# BitBeacon_Emitter.net
KiCad netlist of a schematic drawn in EAGLE
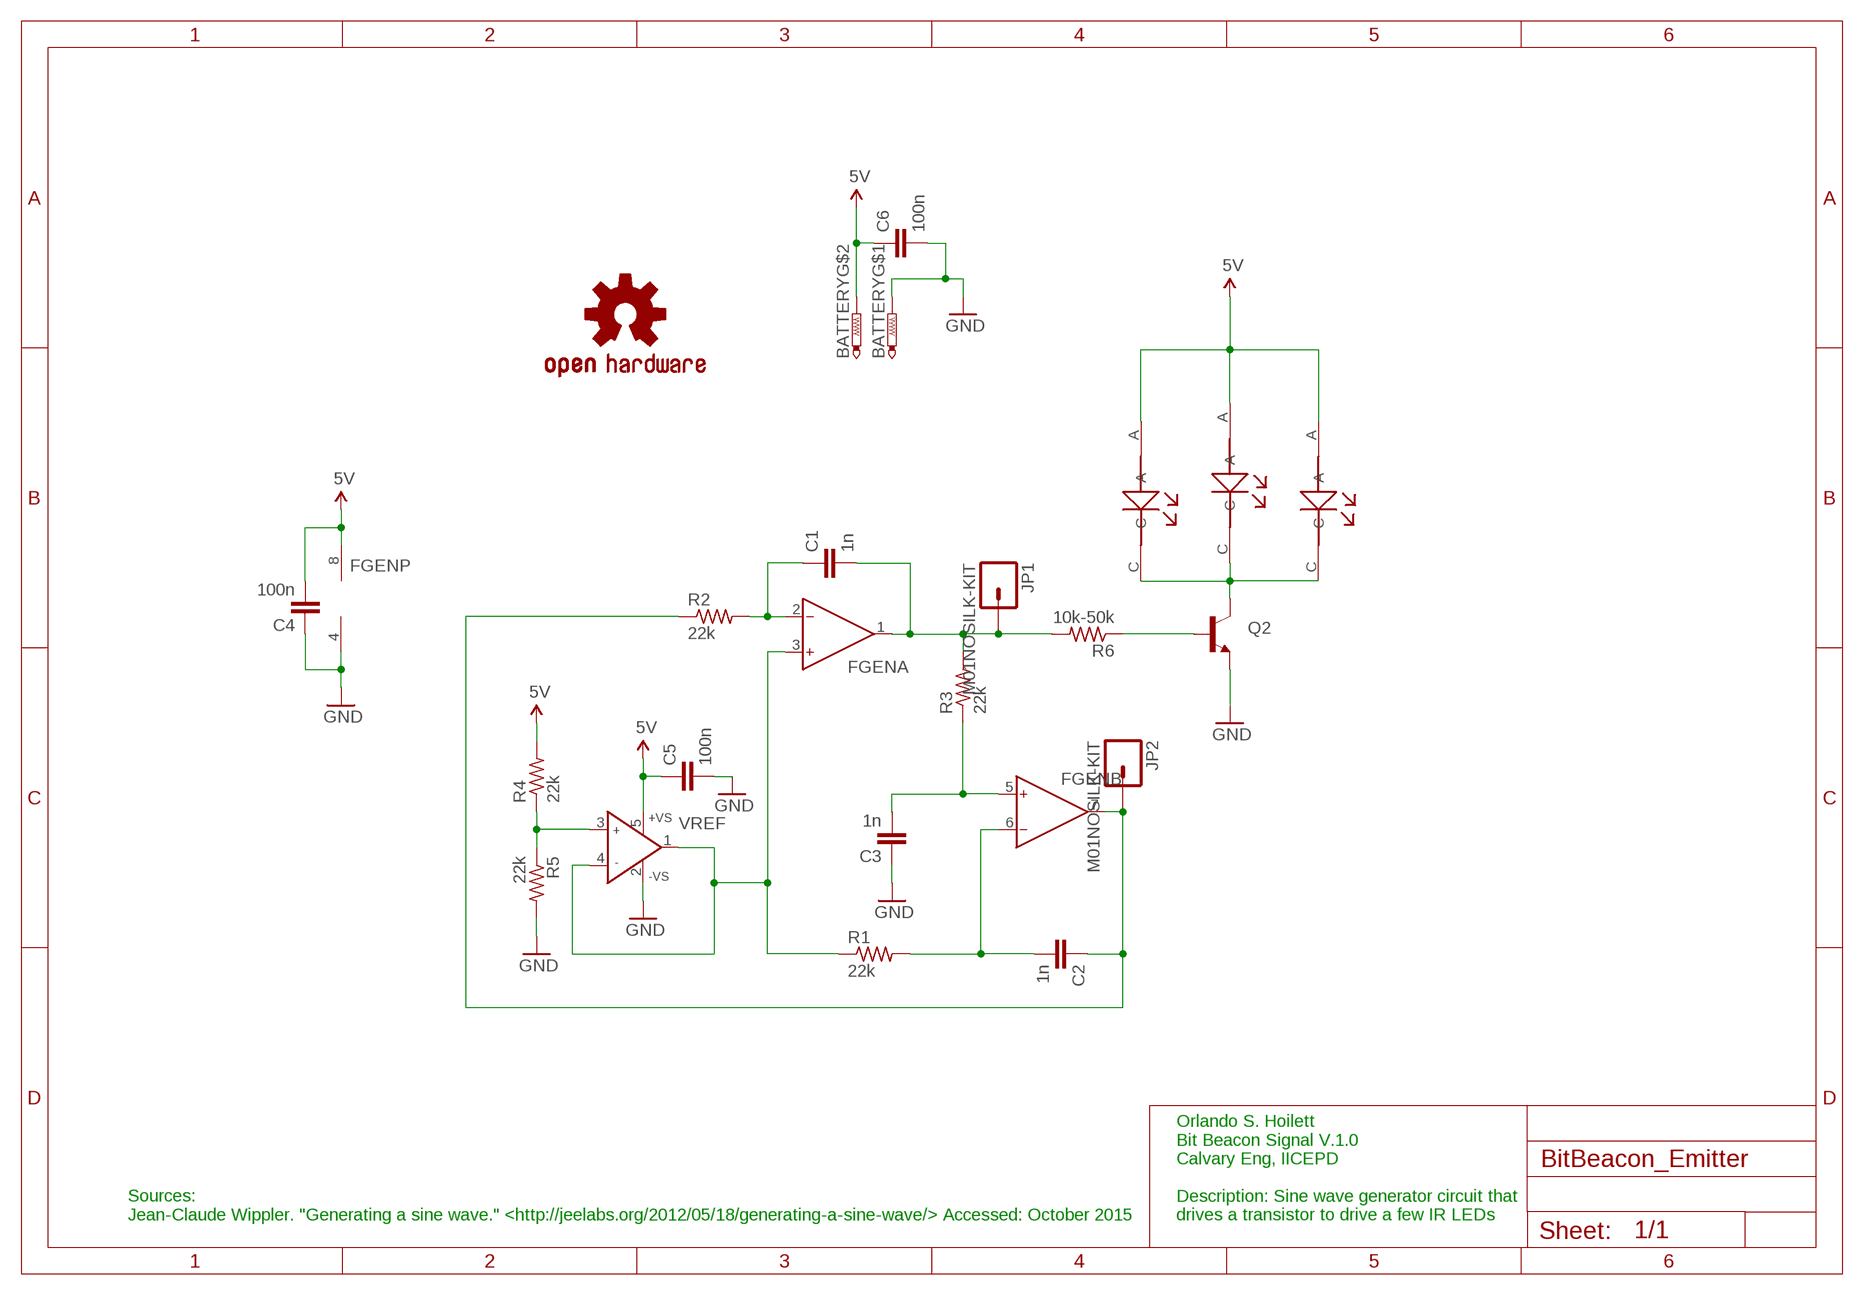
[diagram p0: schematic, sheet 1]

(export (version "E")
  (design (tool "Eeschema 10.0.6"))
  (components
    (comp (ref "BATTERY")
      (value "BATT-CONNECT")
      (footprint "eagle-import:HOLE")
      (libsource (lib "eagle-import") (part "BATT-CONNECT"))
    )
    (comp (ref "C1")
      (value "1n")
      (footprint "eagle-import:C0402")
      (libsource (lib "eagle-import") (part "C-EUC0402"))
    )
    (comp (ref "C2")
      (value "1n")
      (footprint "eagle-import:C0402")
      (libsource (lib "eagle-import") (part "C-EUC0402"))
    )
    (comp (ref "C3")
      (value "1n")
      (footprint "eagle-import:C0402")
      (libsource (lib "eagle-import") (part "C-EUC0402"))
    )
    (comp (ref "C4")
      (value "100n")
      (footprint "eagle-import:C0402")
      (libsource (lib "eagle-import") (part "C-EUC0402"))
    )
    (comp (ref "C5")
      (value "100n")
      (footprint "eagle-import:C0402")
      (libsource (lib "eagle-import") (part "C-EUC0402"))
    )
    (comp (ref "C6")
      (value "100n")
      (footprint "eagle-import:C0402")
      (libsource (lib "eagle-import") (part "C-EUC0402"))
    )
    (comp (ref "FGEN")
      (value "AD8607RM")
      (footprint "eagle-import:MSOP08")
      (fields (field (name "MF") "ALTERA CORPORATION") (field (name "MPN") "AD8607ARMZ-REEL"))
      (libsource (lib "eagle-import") (part "AD8607RM"))
    )
    (comp (ref "JP1")
      (value "M01NOSILK-KIT")
      (footprint "eagle-import:1X01NS-KIT")
      (libsource (lib "eagle-import") (part "M01NOSILK-KIT"))
    )
    (comp (ref "JP2")
      (value "M01NOSILK-KIT")
      (footprint "eagle-import:1X01NS-KIT")
      (libsource (lib "eagle-import") (part "M01NOSILK-KIT"))
    )
    (comp (ref "LED1")
      (value "LED")
      (footprint "eagle-import:LED")
      (libsource (lib "eagle-import") (part "LED"))
    )
    (comp (ref "LED2")
      (value "LED")
      (footprint "eagle-import:LED")
      (libsource (lib "eagle-import") (part "LED"))
    )
    (comp (ref "LED3")
      (value "LED")
      (footprint "eagle-import:LED")
      (libsource (lib "eagle-import") (part "LED"))
    )
    (comp (ref "LOGO1")
      (value "OSHW-LOGOS")
      (footprint "eagle-import:OSHW-LOGO-S")
      (libsource (lib "eagle-import") (part "OSHW-LOGOS"))
    )
    (comp (ref "Q2")
      (value "TRANSISTOR_NPN2N3904")
      (footprint "eagle-import:TO-92")
      (libsource (lib "eagle-import") (part "TRANSISTOR_NPN2N3904"))
    )
    (comp (ref "R1")
      (value "22k")
      (footprint "eagle-import:R0402")
      (libsource (lib "eagle-import") (part "R-US_R0402"))
    )
    (comp (ref "R2")
      (value "22k")
      (footprint "eagle-import:R0402")
      (libsource (lib "eagle-import") (part "R-US_R0402"))
    )
    (comp (ref "R3")
      (value "22k")
      (footprint "eagle-import:R0402")
      (libsource (lib "eagle-import") (part "R-US_R0402"))
    )
    (comp (ref "R4")
      (value "22k")
      (footprint "eagle-import:R0402")
      (libsource (lib "eagle-import") (part "R-US_R0402"))
    )
    (comp (ref "R5")
      (value "22k")
      (footprint "eagle-import:R0402")
      (libsource (lib "eagle-import") (part "R-US_R0402"))
    )
    (comp (ref "R6")
      (value "10k-50k")
      (footprint "eagle-import:R0402")
      (libsource (lib "eagle-import") (part "R-US_R0402"))
    )
    (comp (ref "VREF")
      (value "AD8603UJ")
      (footprint "eagle-import:SOT23-5")
      (fields (field (name "MF") "ALTERA CORPORATION") (field (name "MPN") "AD8603AUJZ-REEL7"))
      (libsource (lib "eagle-import") (part "AD8603UJ"))
    )
  )
  (nets
    (net (code "1") (name "5V") (class "Default")
      (node (ref "BATTERY") (pin "P$2") (pinfunction "TP_P$2") (pintype "input"))
      (node (ref "C4") (pin "2") (pinfunction "2_2") (pintype "passive"))
      (node (ref "C5") (pin "1") (pinfunction "1_1") (pintype "passive"))
      (node (ref "C6") (pin "1") (pinfunction "1_1") (pintype "passive"))
      (node (ref "FGEN") (pin "8") (pinfunction "V+_8") (pintype "power_in"))
      (node (ref "LED1") (pin "A") (pinfunction "A_A") (pintype "bidirectional"))
      (node (ref "LED2") (pin "A") (pinfunction "A_A") (pintype "bidirectional"))
      (node (ref "LED3") (pin "A") (pinfunction "A_A") (pintype "bidirectional"))
      (node (ref "R4") (pin "2") (pinfunction "2_2") (pintype "passive"))
      (node (ref "VREF") (pin "5") (pinfunction "+VS_5") (pintype "input"))
    )
    (net (code "2") (name "GND") (class "Default")
      (node (ref "BATTERY") (pin "P$1") (pinfunction "TP_P$1") (pintype "input"))
      (node (ref "C3") (pin "1") (pinfunction "1_1") (pintype "passive"))
      (node (ref "C4") (pin "1") (pinfunction "1_1") (pintype "passive"))
      (node (ref "C5") (pin "2") (pinfunction "2_2") (pintype "passive"))
      (node (ref "C6") (pin "2") (pinfunction "2_2") (pintype "passive"))
      (node (ref "FGEN") (pin "4") (pinfunction "V-_4") (pintype "power_in"))
      (node (ref "Q2") (pin "1") (pinfunction "E_1") (pintype "passive"))
      (node (ref "R5") (pin "2") (pinfunction "2_2") (pintype "passive"))
      (node (ref "VREF") (pin "2") (pinfunction "-VS_2") (pintype "input"))
    )
    (net (code "3") (name "Net-(FGENA-IN+)") (class "Default")
      (node (ref "FGEN") (pin "3") (pinfunction "IN+_3") (pintype "input"))
      (node (ref "R1") (pin "1") (pinfunction "1_1") (pintype "passive"))
      (node (ref "VREF") (pin "1") (pinfunction "OUT_1") (pintype "output"))
      (node (ref "VREF") (pin "4") (pinfunction "IN-_4") (pintype "input"))
    )
    (net (code "4") (name "Net-(FGENA-IN-)") (class "Default")
      (node (ref "C1") (pin "1") (pinfunction "1_1") (pintype "passive"))
      (node (ref "FGEN") (pin "2") (pinfunction "IN-_2") (pintype "input"))
      (node (ref "R2") (pin "2") (pinfunction "2_2") (pintype "passive"))
    )
    (net (code "5") (name "Net-(FGENA-OUT)") (class "Default")
      (node (ref "C1") (pin "2") (pinfunction "2_2") (pintype "passive"))
      (node (ref "FGEN") (pin "1") (pinfunction "OUT_1") (pintype "output"))
      (node (ref "JP1") (pin "1") (pinfunction "1_1") (pintype "passive"))
      (node (ref "R3") (pin "2") (pinfunction "2_2") (pintype "passive"))
      (node (ref "R6") (pin "2") (pinfunction "2_2") (pintype "passive"))
    )
    (net (code "6") (name "Net-(FGENB-IN+)") (class "Default")
      (node (ref "C3") (pin "2") (pinfunction "2_2") (pintype "passive"))
      (node (ref "FGEN") (pin "5") (pinfunction "IN+_5") (pintype "input"))
      (node (ref "R3") (pin "1") (pinfunction "1_1") (pintype "passive"))
    )
    (net (code "7") (name "Net-(FGENB-IN-)") (class "Default")
      (node (ref "C2") (pin "2") (pinfunction "2_2") (pintype "passive"))
      (node (ref "FGEN") (pin "6") (pinfunction "IN-_6") (pintype "input"))
      (node (ref "R1") (pin "2") (pinfunction "2_2") (pintype "passive"))
    )
    (net (code "8") (name "Net-(FGENB-OUT)") (class "Default")
      (node (ref "C2") (pin "1") (pinfunction "1_1") (pintype "passive"))
      (node (ref "FGEN") (pin "7") (pinfunction "OUT_7") (pintype "output"))
      (node (ref "JP2") (pin "1") (pinfunction "1_1") (pintype "passive"))
      (node (ref "R2") (pin "1") (pinfunction "1_1") (pintype "passive"))
    )
    (net (code "9") (name "Net-(Q2-B)") (class "Default")
      (node (ref "Q2") (pin "2") (pinfunction "B_2") (pintype "passive"))
      (node (ref "R6") (pin "1") (pinfunction "1_1") (pintype "passive"))
    )
    (net (code "10") (name "Net-(Q2-C)") (class "Default")
      (node (ref "LED1") (pin "C") (pinfunction "C_C") (pintype "bidirectional"))
      (node (ref "LED2") (pin "C") (pinfunction "C_C") (pintype "bidirectional"))
      (node (ref "LED3") (pin "C") (pinfunction "C_C") (pintype "bidirectional"))
      (node (ref "Q2") (pin "3") (pinfunction "C_3") (pintype "passive"))
    )
    (net (code "11") (name "Net-(VREF-IN+)") (class "Default")
      (node (ref "R4") (pin "1") (pinfunction "1_1") (pintype "passive"))
      (node (ref "R5") (pin "1") (pinfunction "1_1") (pintype "passive"))
      (node (ref "VREF") (pin "3") (pinfunction "IN+_3") (pintype "input"))
    )
  )
)
